# barcamp_water.net
KiCad netlist of a schematic drawn in EAGLE
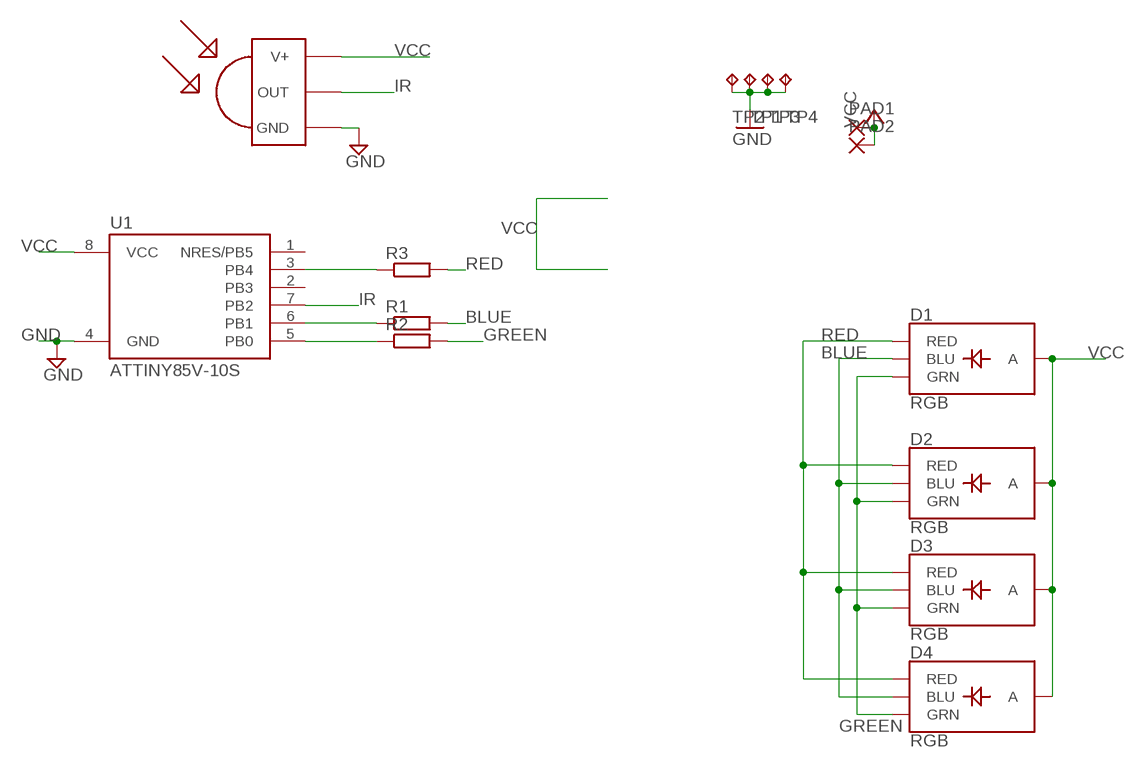
[diagram p0: schematic, sheet 1]

(export (version "E")
  (design (tool "Eeschema 10.0.6"))
  (components
    (comp (ref "D1")
      (value "RGB")
      (footprint "eagle-import:P-LCC-4-3")
      (libsource (lib "eagle-import") (part "LED-RGB-CAPLCC"))
    )
    (comp (ref "D2")
      (value "RGB")
      (footprint "eagle-import:P-LCC-4-3")
      (libsource (lib "eagle-import") (part "LED-RGB-CAPLCC"))
    )
    (comp (ref "D3")
      (value "RGB")
      (footprint "eagle-import:P-LCC-4-3")
      (libsource (lib "eagle-import") (part "LED-RGB-CAPLCC"))
    )
    (comp (ref "D4")
      (value "RGB")
      (footprint "eagle-import:P-LCC-4-3")
      (libsource (lib "eagle-import") (part "LED-RGB-CAPLCC"))
    )
    (comp (ref "PAD1")
      (value "3,17/1,3")
      (footprint "eagle-import:3,17_1,3")
      (libsource (lib "eagle-import") (part "3,17/1,3"))
    )
    (comp (ref "PAD2")
      (value "3,17/1,3")
      (footprint "eagle-import:3,17_1,3")
      (libsource (lib "eagle-import") (part "3,17/1,3"))
    )
    (comp (ref "R1")
      (value "12ohm")
      (footprint "eagle-import:R0603")
      (libsource (lib "eagle-import") (part "R-EU_R0603"))
    )
    (comp (ref "R2")
      (value "12ohm")
      (footprint "eagle-import:R0603")
      (libsource (lib "eagle-import") (part "R-EU_R0603"))
    )
    (comp (ref "R3")
      (value "R-EU_R0603")
      (footprint "eagle-import:R0603")
      (libsource (lib "eagle-import") (part "R-EU_R0603"))
    )
    (comp (ref "TP1")
      (value "TPTP20SQ")
      (footprint "eagle-import:TP20SQ")
      (libsource (lib "eagle-import") (part "TPTP20SQ"))
    )
    (comp (ref "TP2")
      (value "TPTP20SQ")
      (footprint "eagle-import:TP20SQ")
      (libsource (lib "eagle-import") (part "TPTP20SQ"))
    )
    (comp (ref "TP3")
      (value "TPTP20SQ")
      (footprint "eagle-import:TP20SQ")
      (libsource (lib "eagle-import") (part "TPTP20SQ"))
    )
    (comp (ref "TP4")
      (value "TPTP20SQ")
      (footprint "eagle-import:TP20SQ")
      (libsource (lib "eagle-import") (part "TPTP20SQ"))
    )
    (comp (ref "U$1")
      (value "TSOP4838")
      (footprint "eagle-import:TSOP18XX")
      (libsource (lib "eagle-import") (part "TSOP4838"))
    )
    (comp (ref "U1")
      (value "ATTINY85V-10S")
      (footprint "eagle-import:SOIC8_EIAJ_208MIL")
      (libsource (lib "eagle-import") (part "ATTINY85SV-10"))
    )
  )
  (nets
    (net (code "1") (name "/BLUE") (class "Default")
      (node (ref "D1") (pin "3") (pinfunction "BLU_3") (pintype "bidirectional"))
      (node (ref "D2") (pin "3") (pinfunction "BLU_3") (pintype "bidirectional"))
      (node (ref "D3") (pin "3") (pinfunction "BLU_3") (pintype "bidirectional"))
      (node (ref "D4") (pin "3") (pinfunction "BLU_3") (pintype "bidirectional"))
      (node (ref "R1") (pin "2") (pinfunction "2_2") (pintype "passive"))
    )
    (net (code "2") (name "/GREEN") (class "Default")
      (node (ref "D1") (pin "2") (pinfunction "GRN_2") (pintype "bidirectional"))
      (node (ref "D2") (pin "2") (pinfunction "GRN_2") (pintype "bidirectional"))
      (node (ref "D3") (pin "2") (pinfunction "GRN_2") (pintype "bidirectional"))
      (node (ref "D4") (pin "2") (pinfunction "GRN_2") (pintype "bidirectional"))
      (node (ref "R2") (pin "2") (pinfunction "2_2") (pintype "passive"))
    )
    (net (code "3") (name "/IR") (class "Default")
      (node (ref "U$1") (pin "OUT") (pinfunction "OUT_OUT") (pintype "bidirectional"))
      (node (ref "U1") (pin "7") (pinfunction "PB2_7") (pintype "bidirectional"))
    )
    (net (code "4") (name "/RED") (class "Default")
      (node (ref "D1") (pin "1") (pinfunction "RED_1") (pintype "bidirectional"))
      (node (ref "D2") (pin "1") (pinfunction "RED_1") (pintype "bidirectional"))
      (node (ref "D3") (pin "1") (pinfunction "RED_1") (pintype "bidirectional"))
      (node (ref "D4") (pin "1") (pinfunction "RED_1") (pintype "bidirectional"))
      (node (ref "R3") (pin "2") (pinfunction "2_2") (pintype "passive"))
    )
    (net (code "5") (name "GND") (class "Default")
      (node (ref "TP1") (pin "TP") (pinfunction "TP_TP") (pintype "input"))
      (node (ref "TP2") (pin "TP") (pinfunction "TP_TP") (pintype "input"))
      (node (ref "TP3") (pin "TP") (pinfunction "TP_TP") (pintype "input"))
      (node (ref "TP4") (pin "TP") (pinfunction "TP_TP") (pintype "input"))
      (node (ref "U$1") (pin "GND") (pinfunction "GND_GND") (pintype "bidirectional"))
      (node (ref "U1") (pin "4") (pinfunction "GND_4") (pintype "power_in"))
    )
    (net (code "6") (name "Net-(U1-PB0)") (class "Default")
      (node (ref "R2") (pin "1") (pinfunction "1_1") (pintype "passive"))
      (node (ref "U1") (pin "5") (pinfunction "PB0_5") (pintype "bidirectional"))
    )
    (net (code "7") (name "Net-(U1-PB1)") (class "Default")
      (node (ref "R1") (pin "1") (pinfunction "1_1") (pintype "passive"))
      (node (ref "U1") (pin "6") (pinfunction "PB1_6") (pintype "bidirectional"))
    )
    (net (code "8") (name "Net-(U1-PB4)") (class "Default")
      (node (ref "R3") (pin "1") (pinfunction "1_1") (pintype "passive"))
      (node (ref "U1") (pin "3") (pinfunction "PB4_3") (pintype "bidirectional"))
    )
    (net (code "9") (name "VCC") (class "Default")
      (node (ref "D1") (pin "4") (pinfunction "A_4") (pintype "bidirectional"))
      (node (ref "D2") (pin "4") (pinfunction "A_4") (pintype "bidirectional"))
      (node (ref "D3") (pin "4") (pinfunction "A_4") (pintype "bidirectional"))
      (node (ref "D4") (pin "4") (pinfunction "A_4") (pintype "bidirectional"))
      (node (ref "PAD1") (pin "1") (pinfunction "P_1") (pintype "passive"))
      (node (ref "PAD2") (pin "1") (pinfunction "P_1") (pintype "passive"))
      (node (ref "U$1") (pin "VCC") (pinfunction "V+_VCC") (pintype "bidirectional"))
      (node (ref "U1") (pin "8") (pinfunction "VCC_8") (pintype "power_in"))
    )
    (net (code "10") (name "unconnected-(U1-NRES{slash}PB5-Pad1)") (class "Default")
      (node (ref "U1") (pin "1") (pinfunction "NRES/PB5_1") (pintype "bidirectional"))
    )
    (net (code "11") (name "unconnected-(U1-PB3-Pad2)") (class "Default")
      (node (ref "U1") (pin "2") (pinfunction "PB3_2") (pintype "bidirectional"))
    )
  )
)
